# tinyI2C.net
KiCad netlist of a schematic drawn in EAGLE
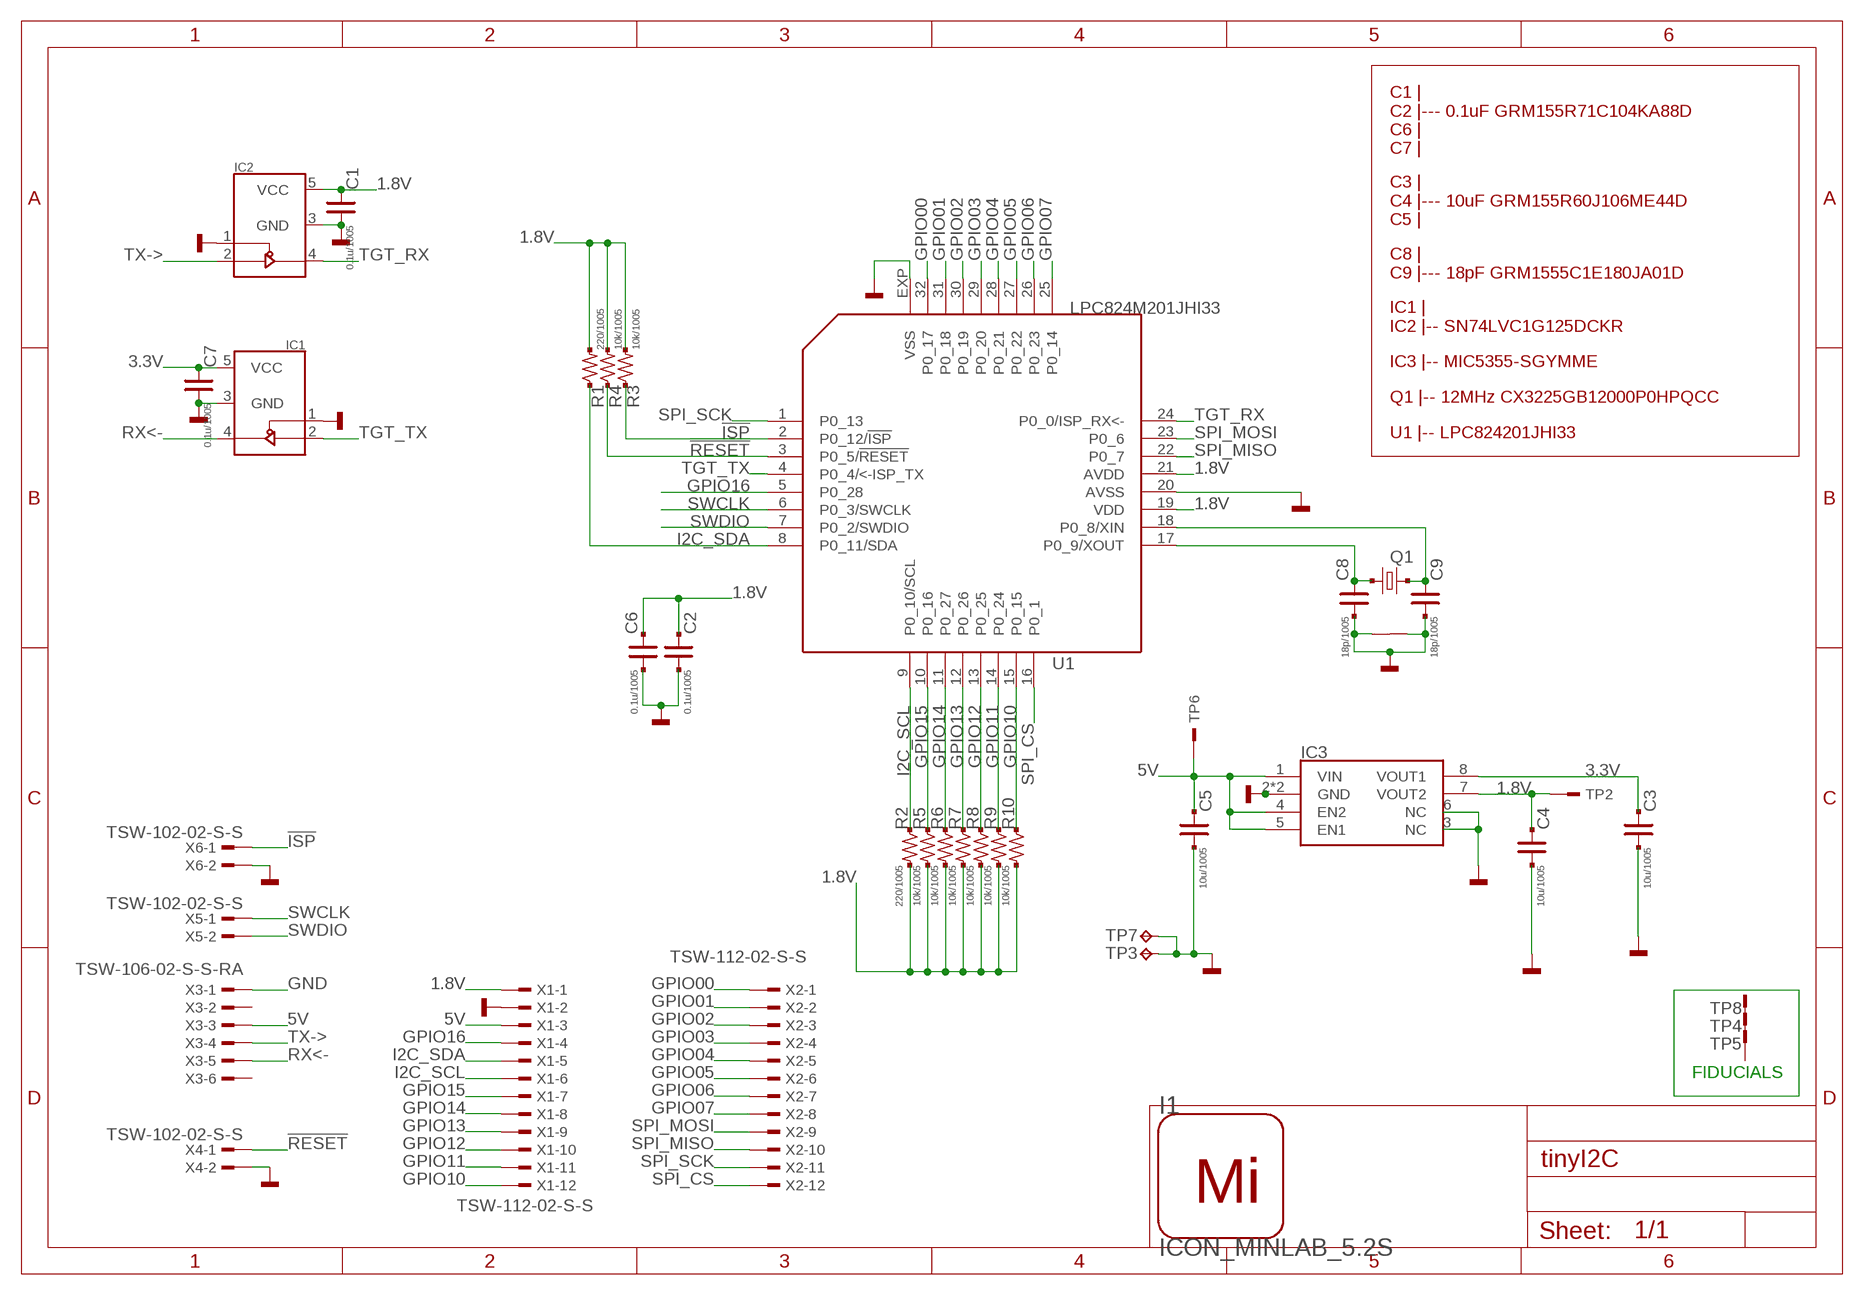
[diagram p0: schematic, sheet 1]

(export (version "E")
  (design (tool "Eeschema 10.0.6"))
  (components
    (comp (ref "C1")
      (value "0.1u/1005")
      (footprint "eagle-import:C0402")
      (libsource (lib "eagle-import") (part "C_SMD__10050.1U"))
    )
    (comp (ref "C2")
      (value "0.1u/1005")
      (footprint "eagle-import:C0402")
      (libsource (lib "eagle-import") (part "C_SMD__10050.1U"))
    )
    (comp (ref "C3")
      (value "10u/1005")
      (footprint "eagle-import:C0402")
      (libsource (lib "eagle-import") (part "C_SMD__100510U"))
    )
    (comp (ref "C4")
      (value "10u/1005")
      (footprint "eagle-import:C0402")
      (libsource (lib "eagle-import") (part "C_SMD__100510U"))
    )
    (comp (ref "C5")
      (value "10u/1005")
      (footprint "eagle-import:C0402")
      (libsource (lib "eagle-import") (part "C_SMD__100510U"))
    )
    (comp (ref "C6")
      (value "0.1u/1005")
      (footprint "eagle-import:C0402")
      (libsource (lib "eagle-import") (part "C_SMD__10050.1U"))
    )
    (comp (ref "C7")
      (value "0.1u/1005")
      (footprint "eagle-import:C0402")
      (libsource (lib "eagle-import") (part "C_SMD__10050.1U"))
    )
    (comp (ref "C8")
      (value "18p/1005")
      (footprint "eagle-import:C0402")
      (libsource (lib "eagle-import") (part "C_SMD__100518P"))
    )
    (comp (ref "C9")
      (value "18p/1005")
      (footprint "eagle-import:C0402")
      (libsource (lib "eagle-import") (part "C_SMD__100518P"))
    )
    (comp (ref "I1")
      (value "ICON_MINLAB_5.2S")
      (footprint "eagle-import:ICON_MINLAB_5.2MM")
      (libsource (lib "eagle-import") (part "ICON_MINLAB_5.2S"))
    )
    (comp (ref "IC1")
      (value "74LVC1G125_SC70")
      (footprint "eagle-import:IC_05_0.635_40MIL")
      (libsource (lib "eagle-import") (part "741G125_SC70LVC"))
    )
    (comp (ref "IC2")
      (value "74LVC1G125_SC70")
      (footprint "eagle-import:IC_05_0.635_40MIL")
      (libsource (lib "eagle-import") (part "741G125_SC70LVC"))
    )
    (comp (ref "IC3")
      (value "IC_LDO_MIC5355_3.3/1.8")
      (footprint "eagle-import:IC_08_0.65_160MIL_EP")
      (libsource (lib "eagle-import") (part "IC_LDO_MIC5355_3.3/1.8"))
    )
    (comp (ref "Q1")
      (value "CRYSTAL4_12M_3225")
      (footprint "eagle-import:CLOCK_3225")
      (libsource (lib "eagle-import") (part "CRYSTAL4__322512M"))
    )
    (comp (ref "R1")
      (value "220/1005")
      (footprint "eagle-import:C0402")
      (libsource (lib "eagle-import") (part "R_US__1005220R"))
    )
    (comp (ref "R2")
      (value "220/1005")
      (footprint "eagle-import:C0402")
      (libsource (lib "eagle-import") (part "R_US__1005220R"))
    )
    (comp (ref "R3")
      (value "10k/1005")
      (footprint "eagle-import:C0402")
      (libsource (lib "eagle-import") (part "R_US__100510K"))
    )
    (comp (ref "R4")
      (value "10k/1005")
      (footprint "eagle-import:C0402")
      (libsource (lib "eagle-import") (part "R_US__100510K"))
    )
    (comp (ref "R5")
      (value "10k/1005")
      (footprint "eagle-import:C0402")
      (libsource (lib "eagle-import") (part "R_US__100510K"))
    )
    (comp (ref "R6")
      (value "10k/1005")
      (footprint "eagle-import:C0402")
      (libsource (lib "eagle-import") (part "R_US__100510K"))
    )
    (comp (ref "R7")
      (value "10k/1005")
      (footprint "eagle-import:C0402")
      (libsource (lib "eagle-import") (part "R_US__100510K"))
    )
    (comp (ref "R8")
      (value "10k/1005")
      (footprint "eagle-import:C0402")
      (libsource (lib "eagle-import") (part "R_US__100510K"))
    )
    (comp (ref "R9")
      (value "10k/1005")
      (footprint "eagle-import:C0402")
      (libsource (lib "eagle-import") (part "R_US__100510K"))
    )
    (comp (ref "R10")
      (value "10k/1005")
      (footprint "eagle-import:C0402")
      (libsource (lib "eagle-import") (part "R_US__100510K"))
    )
    (comp (ref "TP2")
      (value "TESTPAD")
      (footprint "eagle-import:TP06RECT")
      (libsource (lib "eagle-import") (part "TESTPAD"))
    )
    (comp (ref "TP3")
      (value "TPTP14R")
      (footprint "eagle-import:TP14R")
      (libsource (lib "eagle-import") (part "TPTP14R"))
    )
    (comp (ref "TP4")
      (value "TESTPAD_F")
      (footprint "eagle-import:FIDUCIAL")
      (libsource (lib "eagle-import") (part "TESTPAD_F"))
    )
    (comp (ref "TP5")
      (value "TESTPAD_F")
      (footprint "eagle-import:FIDUCIAL")
      (libsource (lib "eagle-import") (part "TESTPAD_F"))
    )
    (comp (ref "TP6")
      (value "TESTPAD")
      (footprint "eagle-import:TP06RECT")
      (libsource (lib "eagle-import") (part "TESTPAD"))
    )
    (comp (ref "TP7")
      (value "TPTP14R")
      (footprint "eagle-import:TP14R")
      (libsource (lib "eagle-import") (part "TPTP14R"))
    )
    (comp (ref "TP8")
      (value "TESTPAD_F")
      (footprint "eagle-import:FIDUCIAL")
      (libsource (lib "eagle-import") (part "TESTPAD_F"))
    )
    (comp (ref "U1")
      (value "LPC824M201JHI33")
      (footprint "eagle-import:HVQFN33")
      (libsource (lib "eagle-import") (part "LPC824M201JHI33"))
    )
    (comp (ref "X1")
      (value "TSW-112-02-S-S")
      (footprint "eagle-import:TSW-112-02-S-S")
      (libsource (lib "eagle-import") (part "TSW-112-02-S-S"))
    )
    (comp (ref "X2")
      (value "TSW-112-02-S-S")
      (footprint "eagle-import:TSW-112-02-S-S")
      (libsource (lib "eagle-import") (part "TSW-112-02-S-S"))
    )
    (comp (ref "X3")
      (value "TSW-106-02-S-S-RA")
      (footprint "eagle-import:TSW-106-02-S-S-RA")
      (libsource (lib "eagle-import") (part "TSW-106-02-S-S-RA"))
    )
    (comp (ref "X4")
      (value "TSW-102-02-S-S")
      (footprint "eagle-import:TSW-102-02-S-S")
      (libsource (lib "eagle-import") (part "TSW-102-02-S-S"))
    )
    (comp (ref "X5")
      (value "TSW-102-02-S-S")
      (footprint "eagle-import:TSW-102-02-S-S")
      (libsource (lib "eagle-import") (part "TSW-102-02-S-S"))
    )
    (comp (ref "X6")
      (value "TSW-102-02-S-S")
      (footprint "eagle-import:TSW-102-02-S-S")
      (libsource (lib "eagle-import") (part "TSW-102-02-S-S"))
    )
  )
  (nets
    (net (code "1") (name "/1.8V") (class "Default")
      (node (ref "C1") (pin "1") (pinfunction "1_1") (pintype "passive"))
      (node (ref "C2") (pin "1") (pinfunction "1_1") (pintype "passive"))
      (node (ref "C4") (pin "1") (pinfunction "1_1") (pintype "passive"))
      (node (ref "C6") (pin "1") (pinfunction "1_1") (pintype "passive"))
      (node (ref "IC2") (pin "5") (pinfunction "VCC_5") (pintype "power_in"))
      (node (ref "IC3") (pin "7") (pinfunction "VOUT2_7") (pintype "bidirectional"))
      (node (ref "R1") (pin "2") (pinfunction "2_2") (pintype "passive"))
      (node (ref "R10") (pin "2") (pinfunction "2_2") (pintype "passive"))
      (node (ref "R2") (pin "2") (pinfunction "2_2") (pintype "passive"))
      (node (ref "R3") (pin "2") (pinfunction "2_2") (pintype "passive"))
      (node (ref "R4") (pin "2") (pinfunction "2_2") (pintype "passive"))
      (node (ref "R5") (pin "2") (pinfunction "2_2") (pintype "passive"))
      (node (ref "R6") (pin "2") (pinfunction "2_2") (pintype "passive"))
      (node (ref "R7") (pin "2") (pinfunction "2_2") (pintype "passive"))
      (node (ref "R8") (pin "2") (pinfunction "2_2") (pintype "passive"))
      (node (ref "R9") (pin "2") (pinfunction "2_2") (pintype "passive"))
      (node (ref "TP2") (pin "TP") (pinfunction "1_TP") (pintype "passive"))
      (node (ref "U1") (pin "19") (pinfunction "VDD_19") (pintype "power_in"))
      (node (ref "U1") (pin "21") (pinfunction "AVDD_21") (pintype "power_in"))
      (node (ref "X1") (pin "1") (pinfunction "1_1") (pintype "passive"))
    )
    (net (code "2") (name "/3.3V") (class "Default")
      (node (ref "C3") (pin "1") (pinfunction "1_1") (pintype "passive"))
      (node (ref "C7") (pin "1") (pinfunction "1_1") (pintype "passive"))
      (node (ref "IC1") (pin "5") (pinfunction "VCC_5") (pintype "power_in"))
      (node (ref "IC3") (pin "8") (pinfunction "VOUT1_8") (pintype "bidirectional"))
    )
    (net (code "3") (name "/5V") (class "Default")
      (node (ref "C5") (pin "1") (pinfunction "1_1") (pintype "passive"))
      (node (ref "IC3") (pin "1") (pinfunction "VIN_1") (pintype "bidirectional"))
      (node (ref "IC3") (pin "4") (pinfunction "EN2_4") (pintype "bidirectional"))
      (node (ref "IC3") (pin "5") (pinfunction "EN1_5") (pintype "bidirectional"))
      (node (ref "TP6") (pin "TP") (pinfunction "1_TP") (pintype "passive"))
      (node (ref "X1") (pin "3") (pinfunction "1_3") (pintype "passive"))
      (node (ref "X3") (pin "3") (pinfunction "1_3") (pintype "passive"))
    )
    (net (code "4") (name "/GPIO00") (class "Default")
      (node (ref "U1") (pin "32") (pinfunction "P0_17_32") (pintype "bidirectional"))
      (node (ref "X2") (pin "1") (pinfunction "1_1") (pintype "passive"))
    )
    (net (code "5") (name "/GPIO01") (class "Default")
      (node (ref "U1") (pin "31") (pinfunction "P0_18_31") (pintype "bidirectional"))
      (node (ref "X2") (pin "2") (pinfunction "1_2") (pintype "passive"))
    )
    (net (code "6") (name "/GPIO02") (class "Default")
      (node (ref "U1") (pin "30") (pinfunction "P0_19_30") (pintype "bidirectional"))
      (node (ref "X2") (pin "3") (pinfunction "1_3") (pintype "passive"))
    )
    (net (code "7") (name "/GPIO03") (class "Default")
      (node (ref "U1") (pin "29") (pinfunction "P0_20_29") (pintype "bidirectional"))
      (node (ref "X2") (pin "4") (pinfunction "1_4") (pintype "passive"))
    )
    (net (code "8") (name "/GPIO04") (class "Default")
      (node (ref "U1") (pin "28") (pinfunction "P0_21_28") (pintype "bidirectional"))
      (node (ref "X2") (pin "5") (pinfunction "1_5") (pintype "passive"))
    )
    (net (code "9") (name "/GPIO05") (class "Default")
      (node (ref "U1") (pin "27") (pinfunction "P0_22_27") (pintype "bidirectional"))
      (node (ref "X2") (pin "6") (pinfunction "1_6") (pintype "passive"))
    )
    (net (code "10") (name "/GPIO06") (class "Default")
      (node (ref "U1") (pin "26") (pinfunction "P0_23_26") (pintype "bidirectional"))
      (node (ref "X2") (pin "7") (pinfunction "1_7") (pintype "passive"))
    )
    (net (code "11") (name "/GPIO07") (class "Default")
      (node (ref "U1") (pin "25") (pinfunction "P0_14_25") (pintype "bidirectional"))
      (node (ref "X2") (pin "8") (pinfunction "1_8") (pintype "passive"))
    )
    (net (code "12") (name "/GPIO10") (class "Default")
      (node (ref "R10") (pin "1") (pinfunction "1_1") (pintype "passive"))
      (node (ref "U1") (pin "15") (pinfunction "P0_15_15") (pintype "bidirectional"))
      (node (ref "X1") (pin "12") (pinfunction "1_12") (pintype "passive"))
    )
    (net (code "13") (name "/GPIO11") (class "Default")
      (node (ref "R9") (pin "1") (pinfunction "1_1") (pintype "passive"))
      (node (ref "U1") (pin "14") (pinfunction "P0_24_14") (pintype "bidirectional"))
      (node (ref "X1") (pin "11") (pinfunction "1_11") (pintype "passive"))
    )
    (net (code "14") (name "/GPIO12") (class "Default")
      (node (ref "R8") (pin "1") (pinfunction "1_1") (pintype "passive"))
      (node (ref "U1") (pin "13") (pinfunction "P0_25_13") (pintype "bidirectional"))
      (node (ref "X1") (pin "10") (pinfunction "1_10") (pintype "passive"))
    )
    (net (code "15") (name "/GPIO13") (class "Default")
      (node (ref "R7") (pin "1") (pinfunction "1_1") (pintype "passive"))
      (node (ref "U1") (pin "12") (pinfunction "P0_26_12") (pintype "bidirectional"))
      (node (ref "X1") (pin "9") (pinfunction "1_9") (pintype "passive"))
    )
    (net (code "16") (name "/GPIO14") (class "Default")
      (node (ref "R6") (pin "1") (pinfunction "1_1") (pintype "passive"))
      (node (ref "U1") (pin "11") (pinfunction "P0_27_11") (pintype "bidirectional"))
      (node (ref "X1") (pin "8") (pinfunction "1_8") (pintype "passive"))
    )
    (net (code "17") (name "/GPIO15") (class "Default")
      (node (ref "R5") (pin "1") (pinfunction "1_1") (pintype "passive"))
      (node (ref "U1") (pin "10") (pinfunction "P0_16_10") (pintype "bidirectional"))
      (node (ref "X1") (pin "7") (pinfunction "1_7") (pintype "passive"))
    )
    (net (code "18") (name "/GPIO16") (class "Default")
      (node (ref "U1") (pin "5") (pinfunction "P0_28_5") (pintype "bidirectional"))
      (node (ref "X1") (pin "4") (pinfunction "1_4") (pintype "passive"))
    )
    (net (code "19") (name "/I2C_SCL") (class "Default")
      (node (ref "R2") (pin "1") (pinfunction "1_1") (pintype "passive"))
      (node (ref "U1") (pin "9") (pinfunction "P0_10/SCL_9") (pintype "bidirectional"))
      (node (ref "X1") (pin "6") (pinfunction "1_6") (pintype "passive"))
    )
    (net (code "20") (name "/I2C_SDA") (class "Default")
      (node (ref "R1") (pin "1") (pinfunction "1_1") (pintype "passive"))
      (node (ref "U1") (pin "8") (pinfunction "P0_11/SDA_8") (pintype "bidirectional"))
      (node (ref "X1") (pin "5") (pinfunction "1_5") (pintype "passive"))
    )
    (net (code "21") (name "/RX<-") (class "Default")
      (node (ref "IC1") (pin "4") (pinfunction "Y_4") (pintype "output"))
      (node (ref "X3") (pin "5") (pinfunction "1_5") (pintype "passive"))
    )
    (net (code "22") (name "/SPI_CS") (class "Default")
      (node (ref "U1") (pin "16") (pinfunction "P0_1_16") (pintype "bidirectional"))
      (node (ref "X2") (pin "12") (pinfunction "1_12") (pintype "passive"))
    )
    (net (code "23") (name "/SPI_MISO") (class "Default")
      (node (ref "U1") (pin "22") (pinfunction "P0_7_22") (pintype "bidirectional"))
      (node (ref "X2") (pin "10") (pinfunction "1_10") (pintype "passive"))
    )
    (net (code "24") (name "/SPI_MOSI") (class "Default")
      (node (ref "U1") (pin "23") (pinfunction "P0_6_23") (pintype "bidirectional"))
      (node (ref "X2") (pin "9") (pinfunction "1_9") (pintype "passive"))
    )
    (net (code "25") (name "/SPI_SCK") (class "Default")
      (node (ref "U1") (pin "1") (pinfunction "P0_13_1") (pintype "bidirectional"))
      (node (ref "X2") (pin "11") (pinfunction "1_11") (pintype "passive"))
    )
    (net (code "26") (name "/SWCLK") (class "Default")
      (node (ref "U1") (pin "6") (pinfunction "P0_3/SWCLK_6") (pintype "bidirectional"))
      (node (ref "X5") (pin "1") (pinfunction "1_1") (pintype "passive"))
    )
    (net (code "27") (name "/SWDIO") (class "Default")
      (node (ref "U1") (pin "7") (pinfunction "P0_2/SWDIO_7") (pintype "bidirectional"))
      (node (ref "X5") (pin "2") (pinfunction "1_2") (pintype "passive"))
    )
    (net (code "28") (name "/TGT_RX") (class "Default")
      (node (ref "IC2") (pin "4") (pinfunction "Y_4") (pintype "output"))
      (node (ref "U1") (pin "24") (pinfunction "P0_0/ISP_RX<-_24") (pintype "bidirectional"))
    )
    (net (code "29") (name "/TGT_TX") (class "Default")
      (node (ref "IC1") (pin "2") (pinfunction "A_2") (pintype "input"))
      (node (ref "U1") (pin "4") (pinfunction "P0_4/<-ISP_TX_4") (pintype "bidirectional"))
    )
    (net (code "30") (name "/TX->") (class "Default")
      (node (ref "IC2") (pin "2") (pinfunction "A_2") (pintype "input"))
      (node (ref "X3") (pin "4") (pinfunction "1_4") (pintype "passive"))
    )
    (net (code "31") (name "/~{ISP}") (class "Default")
      (node (ref "R3") (pin "1") (pinfunction "1_1") (pintype "passive"))
      (node (ref "U1") (pin "2") (pinfunction "P0_12/~{ISP}_2") (pintype "bidirectional"))
      (node (ref "X6") (pin "1") (pinfunction "1_1") (pintype "passive"))
    )
    (net (code "32") (name "/~{RESET}") (class "Default")
      (node (ref "R4") (pin "1") (pinfunction "1_1") (pintype "passive"))
      (node (ref "U1") (pin "3") (pinfunction "P0_5/~{RESET}_3") (pintype "bidirectional"))
      (node (ref "X4") (pin "1") (pinfunction "1_1") (pintype "passive"))
    )
    (net (code "33") (name "GND") (class "Default")
      (node (ref "C1") (pin "2") (pinfunction "2_2") (pintype "passive"))
      (node (ref "C2") (pin "2") (pinfunction "2_2") (pintype "passive"))
      (node (ref "C3") (pin "2") (pinfunction "2_2") (pintype "passive"))
      (node (ref "C4") (pin "2") (pinfunction "2_2") (pintype "passive"))
      (node (ref "C5") (pin "2") (pinfunction "2_2") (pintype "passive"))
      (node (ref "C6") (pin "2") (pinfunction "2_2") (pintype "passive"))
      (node (ref "C7") (pin "2") (pinfunction "2_2") (pintype "passive"))
      (node (ref "C8") (pin "2") (pinfunction "2_2") (pintype "passive"))
      (node (ref "C9") (pin "2") (pinfunction "2_2") (pintype "passive"))
      (node (ref "IC1") (pin "1") (pinfunction "~{OE}_1") (pintype "input"))
      (node (ref "IC1") (pin "3") (pinfunction "GND_3") (pintype "power_in"))
      (node (ref "IC2") (pin "1") (pinfunction "~{OE}_1") (pintype "input"))
      (node (ref "IC2") (pin "3") (pinfunction "GND_3") (pintype "power_in"))
      (node (ref "IC3") (pin "2") (pinfunction "GND_2") (pintype "bidirectional"))
      (node (ref "IC3") (pin "3") (pinfunction "NC_3") (pintype "bidirectional"))
      (node (ref "IC3") (pin "6") (pinfunction "NC_6") (pintype "bidirectional"))
      (node (ref "IC3") (pin "EXP") (pinfunction "GND_EXP") (pintype "bidirectional"))
      (node (ref "Q1") (pin "2") (pinfunction "P$1_2") (pintype "bidirectional"))
      (node (ref "Q1") (pin "4") (pinfunction "P$2_4") (pintype "bidirectional"))
      (node (ref "TP3") (pin "TP") (pinfunction "TP_TP") (pintype "input"))
      (node (ref "TP7") (pin "TP") (pinfunction "TP_TP") (pintype "input"))
      (node (ref "U1") (pin "20") (pinfunction "AVSS_20") (pintype "power_in"))
      (node (ref "U1") (pin "EXP") (pinfunction "VSS_EXP") (pintype "power_in"))
      (node (ref "X1") (pin "2") (pinfunction "1_2") (pintype "passive"))
      (node (ref "X3") (pin "1") (pinfunction "1_1") (pintype "passive"))
      (node (ref "X4") (pin "2") (pinfunction "1_2") (pintype "passive"))
      (node (ref "X6") (pin "2") (pinfunction "1_2") (pintype "passive"))
    )
    (net (code "34") (name "Net-(Q1-2)") (class "Default")
      (node (ref "C9") (pin "1") (pinfunction "1_1") (pintype "passive"))
      (node (ref "Q1") (pin "3") (pinfunction "2_3") (pintype "passive"))
      (node (ref "U1") (pin "18") (pinfunction "P0_8/XIN_18") (pintype "bidirectional"))
    )
    (net (code "35") (name "Net-(U1-P0_9{slash}XOUT)") (class "Default")
      (node (ref "C8") (pin "1") (pinfunction "1_1") (pintype "passive"))
      (node (ref "Q1") (pin "1") (pinfunction "1_1") (pintype "passive"))
      (node (ref "U1") (pin "17") (pinfunction "P0_9/XOUT_17") (pintype "bidirectional"))
    )
    (net (code "36") (name "unconnected-(TP4-1-PadTP)") (class "Default")
      (node (ref "TP4") (pin "TP") (pinfunction "1_TP") (pintype "passive"))
    )
    (net (code "37") (name "unconnected-(TP5-1-PadTP)") (class "Default")
      (node (ref "TP5") (pin "TP") (pinfunction "1_TP") (pintype "passive"))
    )
    (net (code "38") (name "unconnected-(TP8-1-PadTP)") (class "Default")
      (node (ref "TP8") (pin "TP") (pinfunction "1_TP") (pintype "passive"))
    )
    (net (code "39") (name "unconnected-(X3B-1-Pad2)") (class "Default")
      (node (ref "X3") (pin "2") (pinfunction "1_2") (pintype "passive"))
    )
    (net (code "40") (name "unconnected-(X3F-1-Pad6)") (class "Default")
      (node (ref "X3") (pin "6") (pinfunction "1_6") (pintype "passive"))
    )
  )
)
